# Display_Schematic.net
KiCad netlist of a schematic drawn in Altium Designer
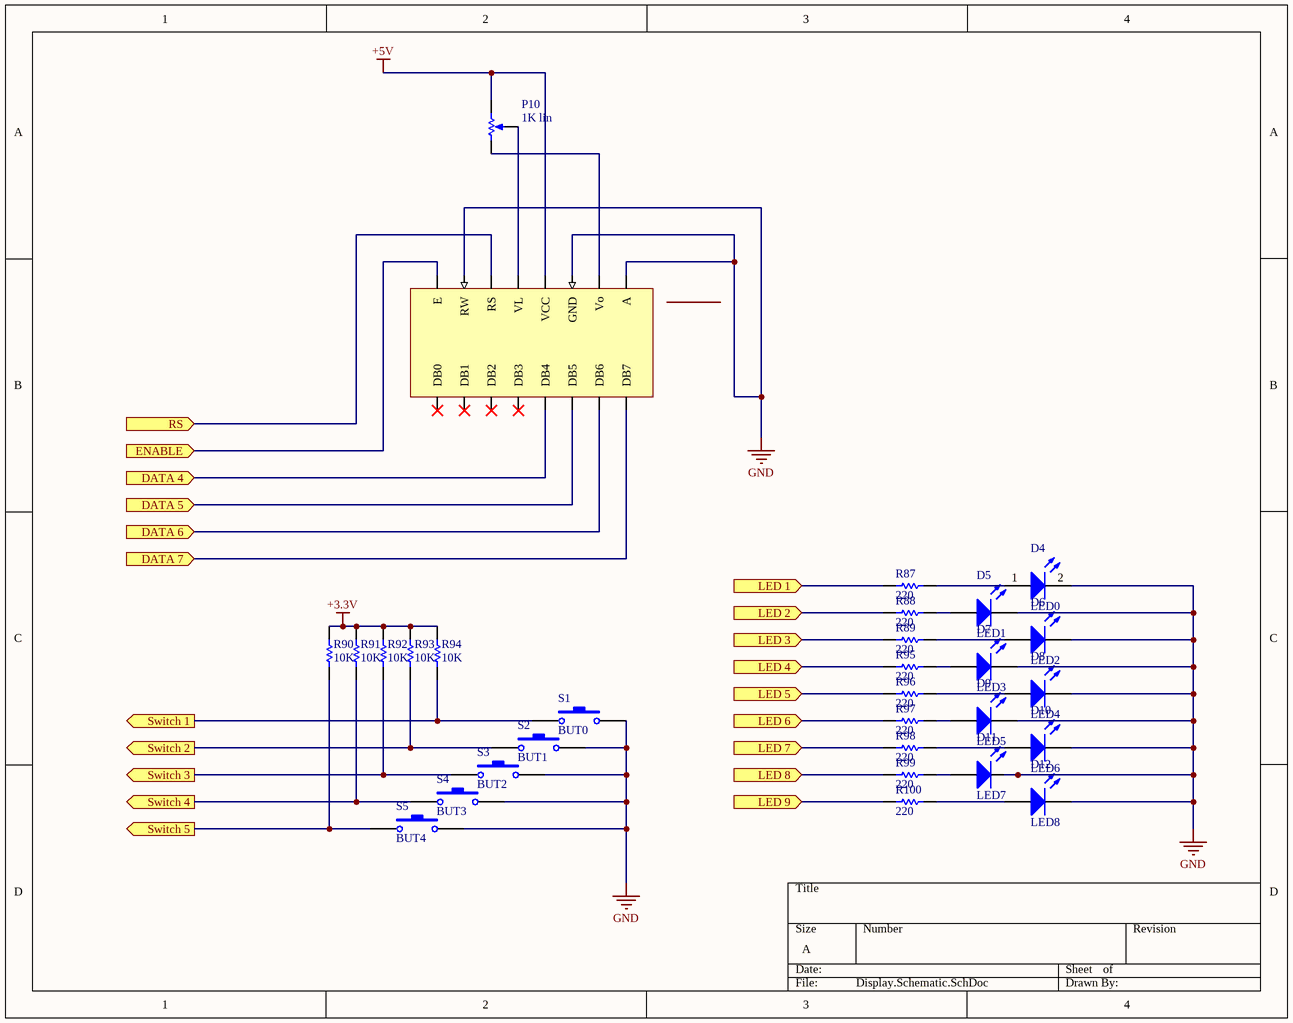
[diagram p0: Display.Schematic.SchDoc]

(export (version "E")
  (design (tool "Eeschema 10.0.6"))
  (components
    (comp (ref "D4")
      (value "LED0")
      (footprint "LED")
      (description "Typical INFRARED GaAs LED")
      (fields (field (name "PUBLISHER") "Altium Limited"))
      (libsource (lib "") (part "LED0_1"))
    )
    (comp (ref "D5")
      (value "LED1")
      (footprint "LED")
      (description "Typical INFRARED GaAs LED")
      (fields (field (name "PUBLISHER") "Altium Limited"))
      (libsource (lib "Miscellaneous Devices") (part "LED0"))
    )
    (comp (ref "D6")
      (value "LED2")
      (footprint "LED")
      (description "Typical INFRARED GaAs LED")
      (fields (field (name "PUBLISHER") "Altium Limited"))
      (libsource (lib "Miscellaneous Devices") (part "LED0"))
    )
    (comp (ref "D7")
      (value "LED3")
      (footprint "LED")
      (description "Typical INFRARED GaAs LED")
      (fields (field (name "PUBLISHER") "Altium Limited"))
      (libsource (lib "Miscellaneous Devices") (part "LED0"))
    )
    (comp (ref "D8")
      (value "LED4")
      (footprint "LED")
      (description "Typical INFRARED GaAs LED")
      (fields (field (name "PUBLISHER") "Altium Limited"))
      (libsource (lib "Miscellaneous Devices") (part "LED0"))
    )
    (comp (ref "D9")
      (value "LED5")
      (footprint "LED")
      (description "Typical INFRARED GaAs LED")
      (fields (field (name "PUBLISHER") "Altium Limited"))
      (libsource (lib "Miscellaneous Devices") (part "LED0"))
    )
    (comp (ref "D10")
      (value "LED6")
      (footprint "LED")
      (description "Typical INFRARED GaAs LED")
      (fields (field (name "PUBLISHER") "Altium Limited"))
      (libsource (lib "Miscellaneous Devices") (part "LED0"))
    )
    (comp (ref "D11")
      (value "LED7")
      (footprint "LED")
      (description "Typical INFRARED GaAs LED")
      (fields (field (name "PUBLISHER") "Altium Limited"))
      (libsource (lib "Miscellaneous Devices") (part "LED0"))
    )
    (comp (ref "D12")
      (value "LED8")
      (footprint "LED")
      (description "Typical INFRARED GaAs LED")
      (fields (field (name "PUBLISHER") "Altium Limited"))
      (libsource (lib "Miscellaneous Devices") (part "LED0"))
    )
    (comp (ref "Display1")
      (value "16x2 LCD")
      (footprint "Display")
      (libsource (lib "display") (part "Display"))
    )
    (comp (ref "P10")
      (value "1K lin")
      (footprint "BOURNS Trim pot")
      (description "Potentiometer")
      (fields (field (name "PUBLISHER") "Altium Limited"))
      (libsource (lib "Miscellaneous Devices") (part "RPot"))
    )
    (comp (ref "R87")
      (value "220")
      (footprint "CAPC1608N")
      (description "Resistor")
      (fields (field (name "PUBLISHER") "Altium Limited"))
      (libsource (lib "Miscellaneous Devices") (part "Res1"))
    )
    (comp (ref "R88")
      (value "220")
      (footprint "CAPC1608N")
      (description "Resistor")
      (fields (field (name "PUBLISHER") "Altium Limited"))
      (libsource (lib "Miscellaneous Devices") (part "Res1"))
    )
    (comp (ref "R89")
      (value "220")
      (footprint "CAPC1608N")
      (description "Resistor")
      (fields (field (name "PUBLISHER") "Altium Limited"))
      (libsource (lib "Miscellaneous Devices") (part "Res1"))
    )
    (comp (ref "R90")
      (value "10K")
      (footprint "CAPC1608N")
      (description "Resistor")
      (fields (field (name "PUBLISHER") "Altium Limited"))
      (libsource (lib "Miscellaneous Devices") (part "Res1"))
    )
    (comp (ref "R91")
      (value "10K")
      (footprint "CAPC1608N")
      (description "Resistor")
      (fields (field (name "PUBLISHER") "Altium Limited"))
      (libsource (lib "Miscellaneous Devices") (part "Res1"))
    )
    (comp (ref "R92")
      (value "10K")
      (footprint "CAPC1608N")
      (description "Resistor")
      (fields (field (name "PUBLISHER") "Altium Limited"))
      (libsource (lib "Miscellaneous Devices") (part "Res1"))
    )
    (comp (ref "R93")
      (value "10K")
      (footprint "CAPC1608N")
      (description "Resistor")
      (fields (field (name "PUBLISHER") "Altium Limited"))
      (libsource (lib "Miscellaneous Devices") (part "Res1"))
    )
    (comp (ref "R94")
      (value "10K")
      (footprint "CAPC1608N")
      (description "Resistor")
      (fields (field (name "PUBLISHER") "Altium Limited"))
      (libsource (lib "Miscellaneous Devices") (part "Res1"))
    )
    (comp (ref "R95")
      (value "220")
      (footprint "CAPC1608N")
      (description "Resistor")
      (fields (field (name "PUBLISHER") "Altium Limited"))
      (libsource (lib "Miscellaneous Devices") (part "Res1"))
    )
    (comp (ref "R96")
      (value "220")
      (footprint "CAPC1608N")
      (description "Resistor")
      (fields (field (name "PUBLISHER") "Altium Limited"))
      (libsource (lib "Miscellaneous Devices") (part "Res1"))
    )
    (comp (ref "R97")
      (value "220")
      (footprint "CAPC1608N")
      (description "Resistor")
      (fields (field (name "PUBLISHER") "Altium Limited"))
      (libsource (lib "Miscellaneous Devices") (part "Res1"))
    )
    (comp (ref "R98")
      (value "220")
      (footprint "CAPC1608N")
      (description "Resistor")
      (fields (field (name "PUBLISHER") "Altium Limited"))
      (libsource (lib "Miscellaneous Devices") (part "Res1"))
    )
    (comp (ref "R99")
      (value "220")
      (footprint "CAPC1608N")
      (description "Resistor")
      (fields (field (name "PUBLISHER") "Altium Limited"))
      (libsource (lib "Miscellaneous Devices") (part "Res1"))
    )
    (comp (ref "R100")
      (value "220")
      (footprint "CAPC1608N")
      (description "Resistor")
      (fields (field (name "PUBLISHER") "Altium Limited"))
      (libsource (lib "Miscellaneous Devices") (part "Res1"))
    )
    (comp (ref "S1")
      (value "BUT0")
      (footprint "PUSH BUTTON")
      (description "Switch")
      (fields (field (name "PUBLISHER") "Altium Limited"))
      (libsource (lib "Miscellaneous Devices") (part "SW-PB"))
    )
    (comp (ref "S2")
      (value "BUT1")
      (footprint "PUSH BUTTON")
      (description "Switch")
      (fields (field (name "PUBLISHER") "Altium Limited"))
      (libsource (lib "Miscellaneous Devices") (part "SW-PB"))
    )
    (comp (ref "S3")
      (value "BUT2")
      (footprint "PUSH BUTTON")
      (description "Switch")
      (fields (field (name "PUBLISHER") "Altium Limited"))
      (libsource (lib "Miscellaneous Devices") (part "SW-PB"))
    )
    (comp (ref "S4")
      (value "BUT3")
      (footprint "PUSH BUTTON")
      (description "Switch")
      (fields (field (name "PUBLISHER") "Altium Limited"))
      (libsource (lib "Miscellaneous Devices") (part "SW-PB"))
    )
    (comp (ref "S5")
      (value "BUT4")
      (footprint "PUSH BUTTON")
      (description "Switch")
      (fields (field (name "PUBLISHER") "Altium Limited"))
      (libsource (lib "Miscellaneous Devices") (part "SW-PB"))
    )
  )
  (nets
    (net (code "1") (name "+3.3V") (class "Default")
      (node (ref "R90") (pin "2") (pinfunction "2_2") (pintype "passive"))
      (node (ref "R91") (pin "2") (pinfunction "2_2") (pintype "passive"))
      (node (ref "R92") (pin "2") (pinfunction "2_2") (pintype "passive"))
      (node (ref "R93") (pin "2") (pinfunction "2_2") (pintype "passive"))
      (node (ref "R94") (pin "2") (pinfunction "2_2") (pintype "passive"))
    )
    (net (code "2") (name "+5V") (class "Default")
      (node (ref "Display1") (pin "2") (pinfunction "VCC_2") (pintype "passive"))
      (node (ref "P10") (pin "2") (pinfunction "BOT_2") (pintype "passive"))
    )
    (net (code "3") (name "/DATA 4") (class "Default")
      (node (ref "Display1") (pin "10") (pinfunction "DB4_10") (pintype "passive"))
    )
    (net (code "4") (name "/DATA 5") (class "Default")
      (node (ref "Display1") (pin "9") (pinfunction "DB5_9") (pintype "passive"))
    )
    (net (code "5") (name "/DATA 6") (class "Default")
      (node (ref "Display1") (pin "8") (pinfunction "DB6_8") (pintype "passive"))
    )
    (net (code "6") (name "/DATA 7") (class "Default")
      (node (ref "Display1") (pin "7") (pinfunction "DB7_7") (pintype "passive"))
    )
    (net (code "7") (name "/ENABLE") (class "Default")
      (node (ref "Display1") (pin "6") (pinfunction "E_6") (pintype "passive"))
    )
    (net (code "8") (name "/LED 1") (class "Default")
      (node (ref "R87") (pin "1") (pinfunction "1_1") (pintype "passive"))
    )
    (net (code "9") (name "/LED 2") (class "Default")
      (node (ref "R88") (pin "1") (pinfunction "1_1") (pintype "passive"))
    )
    (net (code "10") (name "/LED 3") (class "Default")
      (node (ref "R89") (pin "1") (pinfunction "1_1") (pintype "passive"))
    )
    (net (code "11") (name "/LED 4") (class "Default")
      (node (ref "R95") (pin "1") (pinfunction "1_1") (pintype "passive"))
    )
    (net (code "12") (name "/LED 5") (class "Default")
      (node (ref "R96") (pin "1") (pinfunction "1_1") (pintype "passive"))
    )
    (net (code "13") (name "/LED 6") (class "Default")
      (node (ref "R97") (pin "1") (pinfunction "1_1") (pintype "passive"))
    )
    (net (code "14") (name "/LED 7") (class "Default")
      (node (ref "R98") (pin "1") (pinfunction "1_1") (pintype "passive"))
    )
    (net (code "15") (name "/LED 8") (class "Default")
      (node (ref "R99") (pin "1") (pinfunction "1_1") (pintype "passive"))
    )
    (net (code "16") (name "/LED 9") (class "Default")
      (node (ref "R100") (pin "1") (pinfunction "1_1") (pintype "passive"))
    )
    (net (code "17") (name "/RS") (class "Default")
      (node (ref "Display1") (pin "4") (pinfunction "RS_4") (pintype "passive"))
    )
    (net (code "18") (name "/Switch 1") (class "Default")
      (node (ref "R94") (pin "1") (pinfunction "1_1") (pintype "passive"))
      (node (ref "S1") (pin "1") (pinfunction "1_1") (pintype "passive"))
    )
    (net (code "19") (name "/Switch 2") (class "Default")
      (node (ref "R93") (pin "1") (pinfunction "1_1") (pintype "passive"))
      (node (ref "S2") (pin "1") (pinfunction "1_1") (pintype "passive"))
    )
    (net (code "20") (name "/Switch 3") (class "Default")
      (node (ref "R92") (pin "1") (pinfunction "1_1") (pintype "passive"))
      (node (ref "S3") (pin "1") (pinfunction "1_1") (pintype "passive"))
    )
    (net (code "21") (name "/Switch 4") (class "Default")
      (node (ref "R91") (pin "1") (pinfunction "1_1") (pintype "passive"))
      (node (ref "S4") (pin "1") (pinfunction "1_1") (pintype "passive"))
    )
    (net (code "22") (name "/Switch 5") (class "Default")
      (node (ref "R90") (pin "1") (pinfunction "1_1") (pintype "passive"))
      (node (ref "S5") (pin "1") (pinfunction "1_1") (pintype "passive"))
    )
    (net (code "23") (name "GND") (class "Default")
      (node (ref "D10") (pin "2") (pinfunction "K_2") (pintype "passive"))
      (node (ref "D11") (pin "2") (pinfunction "K_2") (pintype "passive"))
      (node (ref "D12") (pin "2") (pinfunction "K_2") (pintype "passive"))
      (node (ref "D4") (pin "2") (pinfunction "K_2") (pintype "passive"))
      (node (ref "D5") (pin "2") (pinfunction "K_2") (pintype "passive"))
      (node (ref "D6") (pin "2") (pinfunction "K_2") (pintype "passive"))
      (node (ref "D7") (pin "2") (pinfunction "K_2") (pintype "passive"))
      (node (ref "D8") (pin "2") (pinfunction "K_2") (pintype "passive"))
      (node (ref "D9") (pin "2") (pinfunction "K_2") (pintype "passive"))
      (node (ref "Display1") (pin "1") (pinfunction "GND_1") (pintype "input"))
      (node (ref "Display1") (pin "16") (pinfunction "A_16") (pintype "passive"))
      (node (ref "Display1") (pin "5") (pinfunction "RW_5") (pintype "input"))
      (node (ref "S1") (pin "2") (pinfunction "2_2") (pintype "passive"))
      (node (ref "S2") (pin "2") (pinfunction "2_2") (pintype "passive"))
      (node (ref "S3") (pin "2") (pinfunction "2_2") (pintype "passive"))
      (node (ref "S4") (pin "2") (pinfunction "2_2") (pintype "passive"))
      (node (ref "S5") (pin "2") (pinfunction "2_2") (pintype "passive"))
    )
    (net (code "24") (name "Net-(D4-A)") (class "Default")
      (node (ref "D4") (pin "1") (pinfunction "A_1") (pintype "passive"))
      (node (ref "R87") (pin "2") (pinfunction "2_2") (pintype "passive"))
    )
    (net (code "25") (name "Net-(D5-A)") (class "Default")
      (node (ref "D5") (pin "1") (pinfunction "A_1") (pintype "passive"))
      (node (ref "R88") (pin "2") (pinfunction "2_2") (pintype "passive"))
    )
    (net (code "26") (name "Net-(D6-A)") (class "Default")
      (node (ref "D6") (pin "1") (pinfunction "A_1") (pintype "passive"))
      (node (ref "R89") (pin "2") (pinfunction "2_2") (pintype "passive"))
    )
    (net (code "27") (name "Net-(D7-A)") (class "Default")
      (node (ref "D7") (pin "1") (pinfunction "A_1") (pintype "passive"))
      (node (ref "R95") (pin "2") (pinfunction "2_2") (pintype "passive"))
    )
    (net (code "28") (name "Net-(D8-A)") (class "Default")
      (node (ref "D8") (pin "1") (pinfunction "A_1") (pintype "passive"))
      (node (ref "R96") (pin "2") (pinfunction "2_2") (pintype "passive"))
    )
    (net (code "29") (name "Net-(D9-A)") (class "Default")
      (node (ref "D9") (pin "1") (pinfunction "A_1") (pintype "passive"))
      (node (ref "R97") (pin "2") (pinfunction "2_2") (pintype "passive"))
    )
    (net (code "30") (name "Net-(D10-A)") (class "Default")
      (node (ref "D10") (pin "1") (pinfunction "A_1") (pintype "passive"))
      (node (ref "R98") (pin "2") (pinfunction "2_2") (pintype "passive"))
    )
    (net (code "31") (name "Net-(D11-A)") (class "Default")
      (node (ref "D11") (pin "1") (pinfunction "A_1") (pintype "passive"))
      (node (ref "R99") (pin "2") (pinfunction "2_2") (pintype "passive"))
    )
    (net (code "32") (name "Net-(D12-A)") (class "Default")
      (node (ref "D12") (pin "1") (pinfunction "A_1") (pintype "passive"))
      (node (ref "R100") (pin "2") (pinfunction "2_2") (pintype "passive"))
    )
    (net (code "33") (name "Net-(Display1-VL)") (class "Default")
      (node (ref "Display1") (pin "3") (pinfunction "VL_3") (pintype "passive"))
      (node (ref "P10") (pin "3") (pinfunction "TAP_3") (pintype "passive"))
    )
    (net (code "34") (name "Net-(Display1-Vo)") (class "Default")
      (node (ref "Display1") (pin "15") (pinfunction "Vo_15") (pintype "passive"))
      (node (ref "P10") (pin "1") (pinfunction "TOP_1") (pintype "passive"))
    )
    (net (code "35") (name "unconnected-(Display1-DB0-Pad14)") (class "Default")
      (node (ref "Display1") (pin "14") (pinfunction "DB0_14") (pintype "passive+no_connect"))
    )
    (net (code "36") (name "unconnected-(Display1-DB1-Pad13)") (class "Default")
      (node (ref "Display1") (pin "13") (pinfunction "DB1_13") (pintype "passive+no_connect"))
    )
    (net (code "37") (name "unconnected-(Display1-DB2-Pad12)") (class "Default")
      (node (ref "Display1") (pin "12") (pinfunction "DB2_12") (pintype "passive+no_connect"))
    )
    (net (code "38") (name "unconnected-(Display1-DB3-Pad11)") (class "Default")
      (node (ref "Display1") (pin "11") (pinfunction "DB3_11") (pintype "passive+no_connect"))
    )
  )
)
